# 3_STM32F334R8T6Board_FilterAndOutputs.net
KiCad netlist of a schematic drawn in Altium Designer
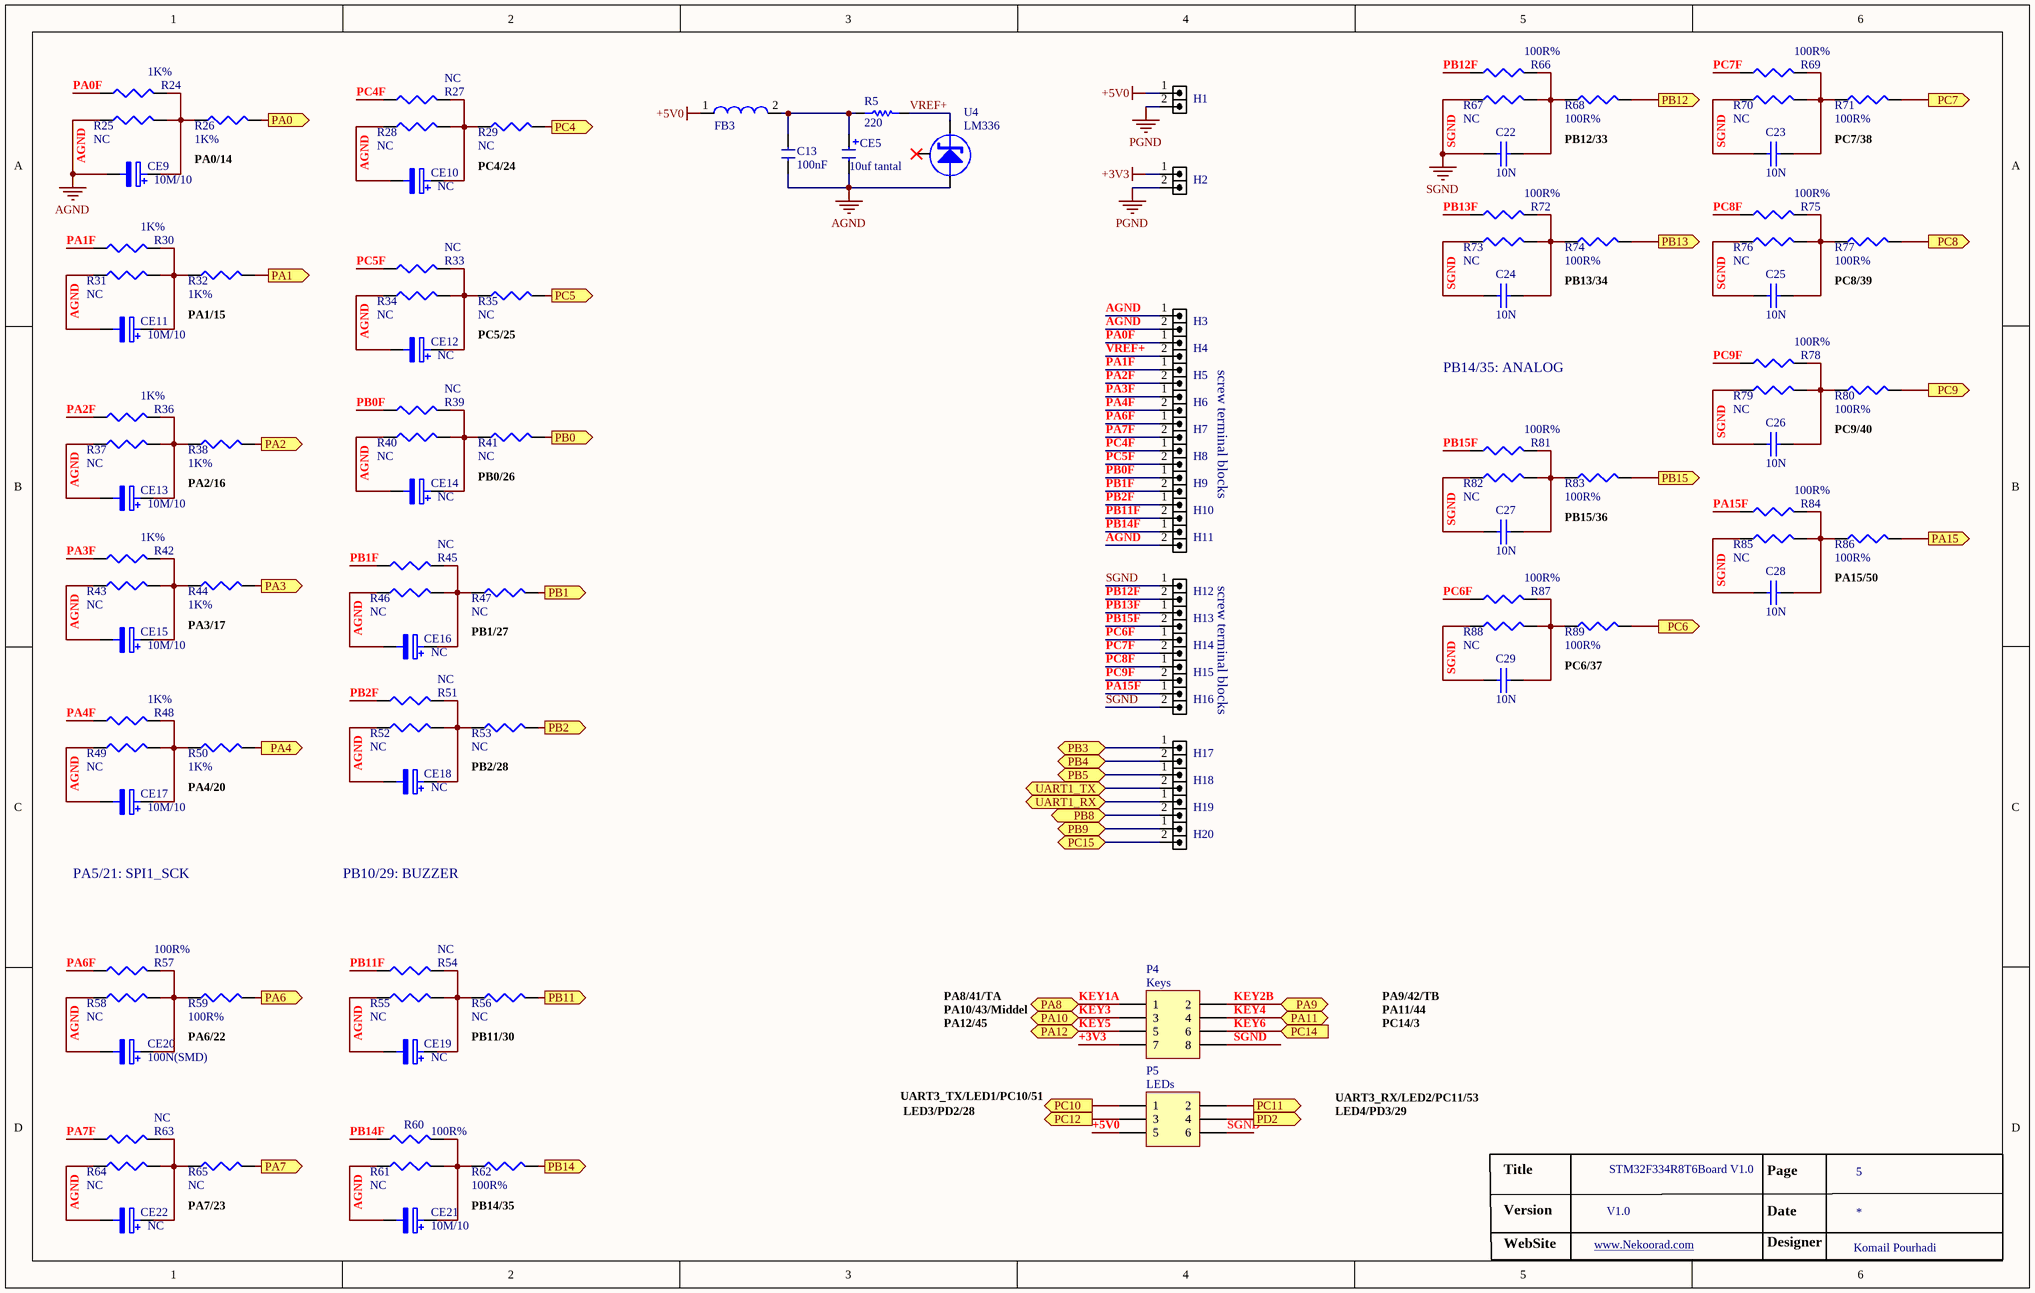
[diagram p0: [3]STM32F334R8T6Board_FilterAndOutputs.SchDoc]

(export (version "E")
  (design (tool "Eeschema 10.0.6"))
  (components
    (comp (ref "C13")
      (value "Comment")
      (footprint "SMD_CAP_1206")
      (fields (field (name "ALTIUM_UNNAMED_1") "100nF"))
      (libsource (lib "DotexGroup_LIB") (part "Capacitor SMD"))
    )
    (comp (ref "C22") (value "10N") (footprint "SMD_CAP_1206") (libsource (lib "*") (part "C")))
    (comp (ref "C23") (value "10N") (footprint "SMD_CAP_1206") (libsource (lib "*") (part "C")))
    (comp (ref "C24") (value "10N") (footprint "SMD_CAP_1206") (libsource (lib "*") (part "C")))
    (comp (ref "C25") (value "10N") (footprint "SMD_CAP_1206") (libsource (lib "*") (part "C")))
    (comp (ref "C26") (value "10N") (footprint "SMD_CAP_1206") (libsource (lib "*") (part "C")))
    (comp (ref "C27") (value "10N") (footprint "SMD_CAP_1206") (libsource (lib "*") (part "C")))
    (comp (ref "C28") (value "10N") (footprint "SMD_CAP_1206") (libsource (lib "*") (part "C")))
    (comp (ref "C29") (value "10N") (footprint "SMD_CAP_1206") (libsource (lib "*") (part "C")))
    (comp (ref "CE5")
      (value "10uf tantal")
      (footprint "cap-e-2")
      (libsource (lib "DotexGroup_LIB") (part "Capacitor Tantalium"))
    )
    (comp (ref "CE9") (value "10M/10") (footprint "CAP E+1206") (libsource (lib "*") (part "E")))
    (comp (ref "CE10") (value "NC") (footprint "CAP E+1206") (libsource (lib "*") (part "E")))
    (comp (ref "CE11") (value "10M/10") (footprint "CAP E+1206") (libsource (lib "*") (part "E")))
    (comp (ref "CE12") (value "NC") (footprint "CAP E+1206") (libsource (lib "*") (part "E")))
    (comp (ref "CE13") (value "10M/10") (footprint "CAP E+1206") (libsource (lib "*") (part "E")))
    (comp (ref "CE14") (value "NC") (footprint "CAP E+1206") (libsource (lib "*") (part "E")))
    (comp (ref "CE15") (value "10M/10") (footprint "CAP E+1206") (libsource (lib "*") (part "E")))
    (comp (ref "CE16") (value "NC") (footprint "CAP E+1206") (libsource (lib "*") (part "E")))
    (comp (ref "CE17") (value "10M/10") (footprint "CAP E+1206") (libsource (lib "*") (part "E")))
    (comp (ref "CE18") (value "NC") (footprint "CAP E+1206") (libsource (lib "*") (part "E")))
    (comp (ref "CE19") (value "NC") (footprint "CAP E+1206") (libsource (lib "*") (part "E")))
    (comp (ref "CE20") (value "100N(SMD)") (footprint "CAP E+1206") (libsource (lib "*") (part "E")))
    (comp (ref "CE21") (value "10M/10") (footprint "CAP E+1206") (libsource (lib "*") (part "E")))
    (comp (ref "CE22") (value "NC") (footprint "CAP E+1206") (libsource (lib "*") (part "E")))
    (comp (ref "FB3")
      (value "Comment")
      (footprint "r4p")
      (libsource (lib "DotexGroup_LIB") (part "Ferrit Bead"))
    )
    (comp (ref "H1")
      (value "HDRM2")
      (footprint "header screw 2*1")
      (description "CONN, HEADER, Male, pitch: 2.54mm, 2POS")
      (libsource (lib "conn_header") (part "HDR_M_1X2"))
    )
    (comp (ref "H2")
      (value "HDRM2")
      (footprint "header screw 2*1")
      (description "CONN, HEADER, Male, pitch: 2.54mm, 2POS")
      (libsource (lib "conn_header") (part "HDR_M_1X2"))
    )
    (comp (ref "H3")
      (value "HDRM2")
      (footprint "header screw 2*1")
      (description "CONN, HEADER, Male, pitch: 2.54mm, 2POS")
      (libsource (lib "conn_header") (part "HDR_M_1X2"))
    )
    (comp (ref "H4")
      (value "HDRM2")
      (footprint "header screw 2*1")
      (description "CONN, HEADER, Male, pitch: 2.54mm, 2POS")
      (libsource (lib "conn_header") (part "HDR_M_1X2"))
    )
    (comp (ref "H5")
      (value "HDRM2")
      (footprint "header screw 2*1")
      (description "CONN, HEADER, Male, pitch: 2.54mm, 2POS")
      (libsource (lib "conn_header") (part "HDR_M_1X2"))
    )
    (comp (ref "H6")
      (value "HDRM2")
      (footprint "header screw 2*1")
      (description "CONN, HEADER, Male, pitch: 2.54mm, 2POS")
      (libsource (lib "conn_header") (part "HDR_M_1X2"))
    )
    (comp (ref "H7")
      (value "HDRM2")
      (footprint "header screw 2*1")
      (description "CONN, HEADER, Male, pitch: 2.54mm, 2POS")
      (libsource (lib "conn_header") (part "HDR_M_1X2"))
    )
    (comp (ref "H8")
      (value "HDRM2")
      (footprint "header screw 2*1")
      (description "CONN, HEADER, Male, pitch: 2.54mm, 2POS")
      (libsource (lib "conn_header") (part "HDR_M_1X2"))
    )
    (comp (ref "H9")
      (value "HDRM2")
      (footprint "header screw 2*1")
      (description "CONN, HEADER, Male, pitch: 2.54mm, 2POS")
      (libsource (lib "conn_header") (part "HDR_M_1X2"))
    )
    (comp (ref "H10")
      (value "HDRM2")
      (footprint "header screw 2*1")
      (description "CONN, HEADER, Male, pitch: 2.54mm, 2POS")
      (libsource (lib "conn_header") (part "HDR_M_1X2"))
    )
    (comp (ref "H11")
      (value "HDRM2")
      (footprint "header screw 2*1")
      (description "CONN, HEADER, Male, pitch: 2.54mm, 2POS")
      (libsource (lib "conn_header") (part "HDR_M_1X2"))
    )
    (comp (ref "H12")
      (value "HDRM2")
      (footprint "header screw 2*1")
      (description "CONN, HEADER, Male, pitch: 2.54mm, 2POS")
      (libsource (lib "conn_header") (part "HDR_M_1X2"))
    )
    (comp (ref "H13")
      (value "HDRM2")
      (footprint "header screw 2*1")
      (description "CONN, HEADER, Male, pitch: 2.54mm, 2POS")
      (libsource (lib "conn_header") (part "HDR_M_1X2"))
    )
    (comp (ref "H14")
      (value "HDRM2")
      (footprint "header screw 2*1")
      (description "CONN, HEADER, Male, pitch: 2.54mm, 2POS")
      (libsource (lib "conn_header") (part "HDR_M_1X2"))
    )
    (comp (ref "H15")
      (value "HDRM2")
      (footprint "header screw 2*1")
      (description "CONN, HEADER, Male, pitch: 2.54mm, 2POS")
      (libsource (lib "conn_header") (part "HDR_M_1X2"))
    )
    (comp (ref "H16")
      (value "HDRM2")
      (footprint "header screw 2*1")
      (description "CONN, HEADER, Male, pitch: 2.54mm, 2POS")
      (libsource (lib "conn_header") (part "HDR_M_1X2"))
    )
    (comp (ref "H17")
      (value "HDRM2")
      (footprint "header screw 2*1")
      (description "CONN, HEADER, Male, pitch: 2.54mm, 2POS")
      (libsource (lib "conn_header") (part "HDR_M_1X2"))
    )
    (comp (ref "H18")
      (value "HDRM2")
      (footprint "header screw 2*1")
      (description "CONN, HEADER, Male, pitch: 2.54mm, 2POS")
      (libsource (lib "conn_header") (part "HDR_M_1X2"))
    )
    (comp (ref "H19")
      (value "HDRM2")
      (footprint "header screw 2*1")
      (description "CONN, HEADER, Male, pitch: 2.54mm, 2POS")
      (libsource (lib "conn_header") (part "HDR_M_1X2"))
    )
    (comp (ref "H20")
      (value "HDRM2")
      (footprint "header screw 2*1")
      (description "CONN, HEADER, Male, pitch: 2.54mm, 2POS")
      (libsource (lib "conn_header") (part "HDR_M_1X2"))
    )
    (comp (ref "P4")
      (value "Keys")
      (footprint "IDC8-BOX")
      (description "Header, 4-Pin, Dual row")
      (fields (field (name "PUBLISHER") "Altium Limited"))
      (libsource (lib "Miscellaneous Connectors") (part "Header 4X2"))
    )
    (comp (ref "P5")
      (value "LEDs")
      (footprint "IDC6-BOX")
      (description "Header, 3-Pin, Dual row")
      (fields (field (name "PUBLISHER") "Altium Limited"))
      (libsource (lib "Miscellaneous Connectors") (part "Header 3X2"))
    )
    (comp (ref "R5")
      (value "220")
      (footprint "RES_1206")
      (description "Resistor")
      (fields (field (name "TOLERANCE") "5%") (field (name "POWER") "1/8 W"))
      (libsource (lib "My Library") (part "Resistor"))
    )
    (comp (ref "R24") (value "1K%") (footprint "RES_1206") (libsource (lib "*") (part "R")))
    (comp (ref "R25") (value "NC") (footprint "RES_1206") (libsource (lib "*") (part "R")))
    (comp (ref "R26") (value "1K%") (footprint "RES_1206") (libsource (lib "*") (part "R")))
    (comp (ref "R27") (value "NC") (footprint "RES_1206") (libsource (lib "*") (part "R")))
    (comp (ref "R28") (value "NC") (footprint "RES_1206") (libsource (lib "*") (part "R")))
    (comp (ref "R29") (value "NC") (footprint "RES_1206") (libsource (lib "*") (part "R")))
    (comp (ref "R30") (value "1K%") (footprint "RES_1206") (libsource (lib "*") (part "R")))
    (comp (ref "R31") (value "NC") (footprint "RES_1206") (libsource (lib "*") (part "R")))
    (comp (ref "R32") (value "1K%") (footprint "RES_1206") (libsource (lib "*") (part "R")))
    (comp (ref "R33") (value "NC") (footprint "RES_1206") (libsource (lib "*") (part "R")))
    (comp (ref "R34") (value "NC") (footprint "RES_1206") (libsource (lib "*") (part "R")))
    (comp (ref "R35") (value "NC") (footprint "RES_1206") (libsource (lib "*") (part "R")))
    (comp (ref "R36") (value "1K%") (footprint "RES_1206") (libsource (lib "*") (part "R")))
    (comp (ref "R37") (value "NC") (footprint "RES_1206") (libsource (lib "*") (part "R")))
    (comp (ref "R38") (value "1K%") (footprint "RES_1206") (libsource (lib "*") (part "R")))
    (comp (ref "R39") (value "NC") (footprint "RES_1206") (libsource (lib "*") (part "R")))
    (comp (ref "R40") (value "NC") (footprint "RES_1206") (libsource (lib "*") (part "R")))
    (comp (ref "R41") (value "NC") (footprint "RES_1206") (libsource (lib "*") (part "R")))
    (comp (ref "R42") (value "1K%") (footprint "RES_1206") (libsource (lib "*") (part "R")))
    (comp (ref "R43") (value "NC") (footprint "RES_1206") (libsource (lib "*") (part "R")))
    (comp (ref "R44") (value "1K%") (footprint "RES_1206") (libsource (lib "*") (part "R")))
    (comp (ref "R45") (value "NC") (footprint "RES_1206") (libsource (lib "*") (part "R")))
    (comp (ref "R46") (value "NC") (footprint "RES_1206") (libsource (lib "*") (part "R")))
    (comp (ref "R47") (value "NC") (footprint "RES_1206") (libsource (lib "*") (part "R")))
    (comp (ref "R48") (value "1K%") (footprint "RES_1206") (libsource (lib "*") (part "R")))
    (comp (ref "R49") (value "NC") (footprint "RES_1206") (libsource (lib "*") (part "R")))
    (comp (ref "R50") (value "1K%") (footprint "RES_1206") (libsource (lib "*") (part "R")))
    (comp (ref "R51") (value "NC") (footprint "RES_1206") (libsource (lib "*") (part "R")))
    (comp (ref "R52") (value "NC") (footprint "RES_1206") (libsource (lib "*") (part "R")))
    (comp (ref "R53") (value "NC") (footprint "RES_1206") (libsource (lib "*") (part "R")))
    (comp (ref "R54") (value "NC") (footprint "RES_1206") (libsource (lib "*") (part "R")))
    (comp (ref "R55") (value "NC") (footprint "RES_1206") (libsource (lib "*") (part "R")))
    (comp (ref "R56") (value "NC") (footprint "RES_1206") (libsource (lib "*") (part "R")))
    (comp (ref "R57") (value "100R%") (footprint "RES_1206") (libsource (lib "*") (part "R")))
    (comp (ref "R58") (value "NC") (footprint "RES_1206") (libsource (lib "*") (part "R")))
    (comp (ref "R59") (value "100R%") (footprint "RES_1206") (libsource (lib "*") (part "R")))
    (comp (ref "R60") (value "100R%") (footprint "RES_1206") (libsource (lib "*") (part "R")))
    (comp (ref "R61") (value "NC") (footprint "RES_1206") (libsource (lib "*") (part "R")))
    (comp (ref "R62") (value "100R%") (footprint "RES_1206") (libsource (lib "*") (part "R")))
    (comp (ref "R63") (value "NC") (footprint "RES_1206") (libsource (lib "*") (part "R")))
    (comp (ref "R64") (value "NC") (footprint "RES_1206") (libsource (lib "*") (part "R")))
    (comp (ref "R65") (value "NC") (footprint "RES_1206") (libsource (lib "*") (part "R")))
    (comp (ref "R66") (value "100R%") (footprint "RES_1206") (libsource (lib "*") (part "R")))
    (comp (ref "R67") (value "NC") (footprint "RES_1206") (libsource (lib "*") (part "R")))
    (comp (ref "R68") (value "100R%") (footprint "RES_1206") (libsource (lib "*") (part "R")))
    (comp (ref "R69") (value "100R%") (footprint "RES_1206") (libsource (lib "*") (part "R")))
    (comp (ref "R70") (value "NC") (footprint "RES_1206") (libsource (lib "*") (part "R")))
    (comp (ref "R71") (value "100R%") (footprint "RES_1206") (libsource (lib "*") (part "R")))
    (comp (ref "R72") (value "100R%") (footprint "RES_1206") (libsource (lib "*") (part "R")))
    (comp (ref "R73") (value "NC") (footprint "RES_1206") (libsource (lib "*") (part "R")))
    (comp (ref "R74") (value "100R%") (footprint "RES_1206") (libsource (lib "*") (part "R")))
    (comp (ref "R75") (value "100R%") (footprint "RES_1206") (libsource (lib "*") (part "R")))
    (comp (ref "R76") (value "NC") (footprint "RES_1206") (libsource (lib "*") (part "R")))
    (comp (ref "R77") (value "100R%") (footprint "RES_1206") (libsource (lib "*") (part "R")))
    (comp (ref "R78") (value "100R%") (footprint "RES_1206") (libsource (lib "*") (part "R")))
    (comp (ref "R79") (value "NC") (footprint "RES_1206") (libsource (lib "*") (part "R")))
    (comp (ref "R80") (value "100R%") (footprint "RES_1206") (libsource (lib "*") (part "R")))
    (comp (ref "R81") (value "100R%") (footprint "RES_1206") (libsource (lib "*") (part "R")))
    (comp (ref "R82") (value "NC") (footprint "RES_1206") (libsource (lib "*") (part "R")))
    (comp (ref "R83") (value "100R%") (footprint "RES_1206") (libsource (lib "*") (part "R")))
    (comp (ref "R84") (value "100R%") (footprint "RES_1206") (libsource (lib "*") (part "R")))
    (comp (ref "R85") (value "NC") (footprint "RES_1206") (libsource (lib "*") (part "R")))
    (comp (ref "R86") (value "100R%") (footprint "RES_1206") (libsource (lib "*") (part "R")))
    (comp (ref "R87") (value "100R%") (footprint "RES_1206") (libsource (lib "*") (part "R")))
    (comp (ref "R88") (value "NC") (footprint "RES_1206") (libsource (lib "*") (part "R")))
    (comp (ref "R89") (value "100R%") (footprint "RES_1206") (libsource (lib "*") (part "R")))
    (comp (ref "U4") (value "LM336") (footprint "LM336") (libsource (lib "MyAltiumLib") (part "LM336")))
  )
  (nets
    (net (code "1") (name "+3V3") (class "Default")
      (node (ref "H2") (pin "1") (pinfunction "1_1") (pintype "passive"))
      (node (ref "P4") (pin "7") (pinfunction "7_7") (pintype "passive"))
    )
    (net (code "2") (name "+5V0") (class "Default")
      (node (ref "FB3") (pin "1") (pinfunction "1_1") (pintype "passive"))
      (node (ref "H1") (pin "1") (pinfunction "1_1") (pintype "passive"))
      (node (ref "P5") (pin "5") (pinfunction "5_5") (pintype "passive"))
    )
    (net (code "3") (name "/KEY1A") (class "Default")
      (node (ref "P4") (pin "1") (pinfunction "1_1") (pintype "passive"))
    )
    (net (code "4") (name "/KEY2B") (class "Default")
      (node (ref "P4") (pin "2") (pinfunction "2_2") (pintype "passive"))
    )
    (net (code "5") (name "/KEY3") (class "Default")
      (node (ref "P4") (pin "3") (pinfunction "3_3") (pintype "passive"))
    )
    (net (code "6") (name "/KEY4") (class "Default")
      (node (ref "P4") (pin "4") (pinfunction "4_4") (pintype "passive"))
    )
    (net (code "7") (name "/KEY5") (class "Default")
      (node (ref "P4") (pin "5") (pinfunction "5_5") (pintype "passive"))
    )
    (net (code "8") (name "/KEY6") (class "Default")
      (node (ref "P4") (pin "6") (pinfunction "6_6") (pintype "passive"))
    )
    (net (code "9") (name "/PA0") (class "Default") (node (ref "R26") (pin "2") (pintype "passive")))
    (net (code "10") (name "/PA0F") (class "Default")
      (node (ref "H4") (pin "1") (pinfunction "1_1") (pintype "passive"))
      (node (ref "R24") (pin "1") (pintype "passive"))
    )
    (net (code "11") (name "/PA1") (class "Default") (node (ref "R32") (pin "2") (pintype "passive")))
    (net (code "12") (name "/PA1F") (class "Default")
      (node (ref "H5") (pin "1") (pinfunction "1_1") (pintype "passive"))
      (node (ref "R30") (pin "1") (pintype "passive"))
    )
    (net (code "13") (name "/PA2") (class "Default") (node (ref "R38") (pin "2") (pintype "passive")))
    (net (code "14") (name "/PA2F") (class "Default")
      (node (ref "H5") (pin "2") (pinfunction "2_2") (pintype "passive"))
      (node (ref "R36") (pin "1") (pintype "passive"))
    )
    (net (code "15") (name "/PA3") (class "Default") (node (ref "R44") (pin "2") (pintype "passive")))
    (net (code "16") (name "/PA3F") (class "Default")
      (node (ref "H6") (pin "1") (pinfunction "1_1") (pintype "passive"))
      (node (ref "R42") (pin "1") (pintype "passive"))
    )
    (net (code "17") (name "/PA4") (class "Default") (node (ref "R50") (pin "2") (pintype "passive")))
    (net (code "18") (name "/PA4F") (class "Default")
      (node (ref "H6") (pin "2") (pinfunction "2_2") (pintype "passive"))
      (node (ref "R48") (pin "1") (pintype "passive"))
    )
    (net (code "19") (name "/PA6") (class "Default") (node (ref "R59") (pin "2") (pintype "passive")))
    (net (code "20") (name "/PA6F") (class "Default")
      (node (ref "H7") (pin "1") (pinfunction "1_1") (pintype "passive"))
      (node (ref "R57") (pin "1") (pintype "passive"))
    )
    (net (code "21") (name "/PA7") (class "Default") (node (ref "R65") (pin "2") (pintype "passive")))
    (net (code "22") (name "/PA7F") (class "Default")
      (node (ref "H7") (pin "2") (pinfunction "2_2") (pintype "passive"))
      (node (ref "R63") (pin "1") (pintype "passive"))
    )
    (net (code "23") (name "/PA15") (class "Default") (node (ref "R86") (pin "2") (pintype "passive")))
    (net (code "24") (name "/PA15F") (class "Default")
      (node (ref "H16") (pin "1") (pinfunction "1_1") (pintype "passive"))
      (node (ref "R84") (pin "1") (pintype "passive"))
    )
    (net (code "25") (name "/PB0") (class "Default") (node (ref "R41") (pin "2") (pintype "passive")))
    (net (code "26") (name "/PB0F") (class "Default")
      (node (ref "H9") (pin "1") (pinfunction "1_1") (pintype "passive"))
      (node (ref "R39") (pin "1") (pintype "passive"))
    )
    (net (code "27") (name "/PB1") (class "Default") (node (ref "R47") (pin "2") (pintype "passive")))
    (net (code "28") (name "/PB1F") (class "Default")
      (node (ref "H9") (pin "2") (pinfunction "2_2") (pintype "passive"))
      (node (ref "R45") (pin "1") (pintype "passive"))
    )
    (net (code "29") (name "/PB2") (class "Default") (node (ref "R53") (pin "2") (pintype "passive")))
    (net (code "30") (name "/PB2F") (class "Default")
      (node (ref "H10") (pin "1") (pinfunction "1_1") (pintype "passive"))
      (node (ref "R51") (pin "1") (pintype "passive"))
    )
    (net (code "31") (name "/PB3") (class "Default")
      (node (ref "H17") (pin "1") (pinfunction "1_1") (pintype "passive"))
    )
    (net (code "32") (name "/PB4") (class "Default")
      (node (ref "H17") (pin "2") (pinfunction "2_2") (pintype "passive"))
    )
    (net (code "33") (name "/PB5") (class "Default")
      (node (ref "H18") (pin "1") (pinfunction "1_1") (pintype "passive"))
    )
    (net (code "34") (name "/PB8") (class "Default")
      (node (ref "H19") (pin "2") (pinfunction "2_2") (pintype "passive"))
    )
    (net (code "35") (name "/PB9") (class "Default")
      (node (ref "H20") (pin "1") (pinfunction "1_1") (pintype "passive"))
    )
    (net (code "36") (name "/PB11") (class "Default") (node (ref "R56") (pin "2") (pintype "passive")))
    (net (code "37") (name "/PB11F") (class "Default")
      (node (ref "H10") (pin "2") (pinfunction "2_2") (pintype "passive"))
      (node (ref "R54") (pin "1") (pintype "passive"))
    )
    (net (code "38") (name "/PB12") (class "Default") (node (ref "R68") (pin "2") (pintype "passive")))
    (net (code "39") (name "/PB12F") (class "Default")
      (node (ref "H12") (pin "2") (pinfunction "2_2") (pintype "passive"))
      (node (ref "R66") (pin "1") (pintype "passive"))
    )
    (net (code "40") (name "/PB13") (class "Default") (node (ref "R74") (pin "2") (pintype "passive")))
    (net (code "41") (name "/PB13F") (class "Default")
      (node (ref "H13") (pin "1") (pinfunction "1_1") (pintype "passive"))
      (node (ref "R72") (pin "1") (pintype "passive"))
    )
    (net (code "42") (name "/PB14") (class "Default") (node (ref "R62") (pin "2") (pintype "passive")))
    (net (code "43") (name "/PB14F") (class "Default")
      (node (ref "H11") (pin "1") (pinfunction "1_1") (pintype "passive"))
      (node (ref "R60") (pin "1") (pintype "passive"))
    )
    (net (code "44") (name "/PB15") (class "Default") (node (ref "R83") (pin "2") (pintype "passive")))
    (net (code "45") (name "/PB15F") (class "Default")
      (node (ref "H13") (pin "2") (pinfunction "2_2") (pintype "passive"))
      (node (ref "R81") (pin "1") (pintype "passive"))
    )
    (net (code "46") (name "/PC4") (class "Default") (node (ref "R29") (pin "2") (pintype "passive")))
    (net (code "47") (name "/PC4F") (class "Default")
      (node (ref "H8") (pin "1") (pinfunction "1_1") (pintype "passive"))
      (node (ref "R27") (pin "1") (pintype "passive"))
    )
    (net (code "48") (name "/PC5") (class "Default") (node (ref "R35") (pin "2") (pintype "passive")))
    (net (code "49") (name "/PC5F") (class "Default")
      (node (ref "H8") (pin "2") (pinfunction "2_2") (pintype "passive"))
      (node (ref "R33") (pin "1") (pintype "passive"))
    )
    (net (code "50") (name "/PC6") (class "Default") (node (ref "R89") (pin "2") (pintype "passive")))
    (net (code "51") (name "/PC6F") (class "Default")
      (node (ref "H14") (pin "1") (pinfunction "1_1") (pintype "passive"))
      (node (ref "R87") (pin "1") (pintype "passive"))
    )
    (net (code "52") (name "/PC7") (class "Default") (node (ref "R71") (pin "2") (pintype "passive")))
    (net (code "53") (name "/PC7F") (class "Default")
      (node (ref "H14") (pin "2") (pinfunction "2_2") (pintype "passive"))
      (node (ref "R69") (pin "1") (pintype "passive"))
    )
    (net (code "54") (name "/PC8") (class "Default") (node (ref "R77") (pin "2") (pintype "passive")))
    (net (code "55") (name "/PC8F") (class "Default")
      (node (ref "H15") (pin "1") (pinfunction "1_1") (pintype "passive"))
      (node (ref "R75") (pin "1") (pintype "passive"))
    )
    (net (code "56") (name "/PC9") (class "Default") (node (ref "R80") (pin "2") (pintype "passive")))
    (net (code "57") (name "/PC9F") (class "Default")
      (node (ref "H15") (pin "2") (pinfunction "2_2") (pintype "passive"))
      (node (ref "R78") (pin "1") (pintype "passive"))
    )
    (net (code "58") (name "/PC10") (class "Default")
      (node (ref "P5") (pin "1") (pinfunction "1_1") (pintype "passive"))
    )
    (net (code "59") (name "/PC11") (class "Default")
      (node (ref "P5") (pin "2") (pinfunction "2_2") (pintype "passive"))
    )
    (net (code "60") (name "/PC12") (class "Default")
      (node (ref "P5") (pin "3") (pinfunction "3_3") (pintype "passive"))
    )
    (net (code "61") (name "/PC15") (class "Default")
      (node (ref "H20") (pin "2") (pinfunction "2_2") (pintype "passive"))
    )
    (net (code "62") (name "/PD2") (class "Default")
      (node (ref "P5") (pin "4") (pinfunction "4_4") (pintype "passive"))
    )
    (net (code "63") (name "/UART1_RX") (class "Default")
      (node (ref "H19") (pin "1") (pinfunction "1_1") (pintype "passive"))
    )
    (net (code "64") (name "/UART1_TX") (class "Default")
      (node (ref "H18") (pin "2") (pinfunction "2_2") (pintype "passive"))
    )
    (net (code "65") (name "/VREF+") (class "Default")
      (node (ref "H4") (pin "2") (pinfunction "2_2") (pintype "passive"))
      (node (ref "R5") (pin "2") (pinfunction "2_2") (pintype "passive"))
      (node (ref "U4") (pin "2") (pintype "passive"))
    )
    (net (code "66") (name "AGND") (class "Default")
      (node (ref "C13") (pin "1") (pintype "passive"))
      (node (ref "CE10") (pin "2") (pintype "passive"))
      (node (ref "CE11") (pin "2") (pintype "passive"))
      (node (ref "CE12") (pin "2") (pintype "passive"))
      (node (ref "CE13") (pin "2") (pintype "passive"))
      (node (ref "CE14") (pin "2") (pintype "passive"))
      (node (ref "CE15") (pin "2") (pintype "passive"))
      (node (ref "CE16") (pin "2") (pintype "passive"))
      (node (ref "CE17") (pin "2") (pintype "passive"))
      (node (ref "CE18") (pin "2") (pintype "passive"))
      (node (ref "CE19") (pin "2") (pintype "passive"))
      (node (ref "CE20") (pin "2") (pintype "passive"))
      (node (ref "CE21") (pin "2") (pintype "passive"))
      (node (ref "CE22") (pin "2") (pintype "passive"))
      (node (ref "CE5") (pin "2") (pintype "passive"))
      (node (ref "CE9") (pin "2") (pintype "passive"))
      (node (ref "H11") (pin "2") (pinfunction "2_2") (pintype "passive"))
      (node (ref "H3") (pin "1") (pinfunction "1_1") (pintype "passive"))
      (node (ref "H3") (pin "2") (pinfunction "2_2") (pintype "passive"))
      (node (ref "R25") (pin "1") (pintype "passive"))
      (node (ref "R28") (pin "1") (pintype "passive"))
      (node (ref "R31") (pin "1") (pintype "passive"))
      (node (ref "R34") (pin "1") (pintype "passive"))
      (node (ref "R37") (pin "1") (pintype "passive"))
      (node (ref "R40") (pin "1") (pintype "passive"))
      (node (ref "R43") (pin "1") (pintype "passive"))
      (node (ref "R46") (pin "1") (pintype "passive"))
      (node (ref "R49") (pin "1") (pintype "passive"))
      (node (ref "R52") (pin "1") (pintype "passive"))
      (node (ref "R55") (pin "1") (pintype "passive"))
      (node (ref "R58") (pin "1") (pintype "passive"))
      (node (ref "R61") (pin "1") (pintype "passive"))
      (node (ref "R64") (pin "1") (pintype "passive"))
      (node (ref "U4") (pin "1") (pintype "passive"))
    )
    (net (code "67") (name "Net-(C13-Pad2)") (class "Default")
      (node (ref "C13") (pin "2") (pintype "passive"))
      (node (ref "CE5") (pin "1") (pintype "passive"))
      (node (ref "FB3") (pin "2") (pinfunction "2_2") (pintype "passive"))
      (node (ref "R5") (pin "1") (pinfunction "1_1") (pintype "passive"))
    )
    (net (code "68") (name "Net-(C22-Pad1)") (class "Default")
      (node (ref "C22") (pin "1") (pintype "passive"))
      (node (ref "R66") (pin "2") (pintype "passive"))
      (node (ref "R67") (pin "2") (pintype "passive"))
      (node (ref "R68") (pin "1") (pintype "passive"))
    )
    (net (code "69") (name "Net-(C23-Pad1)") (class "Default")
      (node (ref "C23") (pin "1") (pintype "passive"))
      (node (ref "R69") (pin "2") (pintype "passive"))
      (node (ref "R70") (pin "2") (pintype "passive"))
      (node (ref "R71") (pin "1") (pintype "passive"))
    )
    (net (code "70") (name "Net-(C24-Pad1)") (class "Default")
      (node (ref "C24") (pin "1") (pintype "passive"))
      (node (ref "R72") (pin "2") (pintype "passive"))
      (node (ref "R73") (pin "2") (pintype "passive"))
      (node (ref "R74") (pin "1") (pintype "passive"))
    )
    (net (code "71") (name "Net-(C25-Pad1)") (class "Default")
      (node (ref "C25") (pin "1") (pintype "passive"))
      (node (ref "R75") (pin "2") (pintype "passive"))
      (node (ref "R76") (pin "2") (pintype "passive"))
      (node (ref "R77") (pin "1") (pintype "passive"))
    )
    (net (code "72") (name "Net-(C26-Pad1)") (class "Default")
      (node (ref "C26") (pin "1") (pintype "passive"))
      (node (ref "R78") (pin "2") (pintype "passive"))
      (node (ref "R79") (pin "2") (pintype "passive"))
      (node (ref "R80") (pin "1") (pintype "passive"))
    )
    (net (code "73") (name "Net-(C27-Pad1)") (class "Default")
      (node (ref "C27") (pin "1") (pintype "passive"))
      (node (ref "R81") (pin "2") (pintype "passive"))
      (node (ref "R82") (pin "2") (pintype "passive"))
      (node (ref "R83") (pin "1") (pintype "passive"))
    )
    (net (code "74") (name "Net-(C28-Pad1)") (class "Default")
      (node (ref "C28") (pin "1") (pintype "passive"))
      (node (ref "R84") (pin "2") (pintype "passive"))
      (node (ref "R85") (pin "2") (pintype "passive"))
      (node (ref "R86") (pin "1") (pintype "passive"))
    )
    (net (code "75") (name "Net-(C29-Pad1)") (class "Default")
      (node (ref "C29") (pin "1") (pintype "passive"))
      (node (ref "R87") (pin "2") (pintype "passive"))
      (node (ref "R88") (pin "2") (pintype "passive"))
      (node (ref "R89") (pin "1") (pintype "passive"))
    )
    (net (code "76") (name "Net-(CE9-Pad1)") (class "Default")
      (node (ref "CE9") (pin "1") (pintype "passive"))
      (node (ref "R24") (pin "2") (pintype "passive"))
      (node (ref "R25") (pin "2") (pintype "passive"))
      (node (ref "R26") (pin "1") (pintype "passive"))
    )
    (net (code "77") (name "Net-(CE10-Pad1)") (class "Default")
      (node (ref "CE10") (pin "1") (pintype "passive"))
      (node (ref "R27") (pin "2") (pintype "passive"))
      (node (ref "R28") (pin "2") (pintype "passive"))
      (node (ref "R29") (pin "1") (pintype "passive"))
    )
    (net (code "78") (name "Net-(CE11-Pad1)") (class "Default")
      (node (ref "CE11") (pin "1") (pintype "passive"))
      (node (ref "R30") (pin "2") (pintype "passive"))
      (node (ref "R31") (pin "2") (pintype "passive"))
      (node (ref "R32") (pin "1") (pintype "passive"))
    )
    (net (code "79") (name "Net-(CE12-Pad1)") (class "Default")
      (node (ref "CE12") (pin "1") (pintype "passive"))
      (node (ref "R33") (pin "2") (pintype "passive"))
      (node (ref "R34") (pin "2") (pintype "passive"))
      (node (ref "R35") (pin "1") (pintype "passive"))
    )
    (net (code "80") (name "Net-(CE13-Pad1)") (class "Default")
      (node (ref "CE13") (pin "1") (pintype "passive"))
      (node (ref "R36") (pin "2") (pintype "passive"))
      (node (ref "R37") (pin "2") (pintype "passive"))
      (node (ref "R38") (pin "1") (pintype "passive"))
    )
    (net (code "81") (name "Net-(CE14-Pad1)") (class "Default")
      (node (ref "CE14") (pin "1") (pintype "passive"))
      (node (ref "R39") (pin "2") (pintype "passive"))
      (node (ref "R40") (pin "2") (pintype "passive"))
      (node (ref "R41") (pin "1") (pintype "passive"))
    )
    (net (code "82") (name "Net-(CE15-Pad1)") (class "Default")
      (node (ref "CE15") (pin "1") (pintype "passive"))
      (node (ref "R42") (pin "2") (pintype "passive"))
      (node (ref "R43") (pin "2") (pintype "passive"))
      (node (ref "R44") (pin "1") (pintype "passive"))
    )
    (net (code "83") (name "Net-(CE16-Pad1)") (class "Default")
      (node (ref "CE16") (pin "1") (pintype "passive"))
      (node (ref "R45") (pin "2") (pintype "passive"))
      (node (ref "R46") (pin "2") (pintype "passive"))
      (node (ref "R47") (pin "1") (pintype "passive"))
    )
    (net (code "84") (name "Net-(CE17-Pad1)") (class "Default")
      (node (ref "CE17") (pin "1") (pintype "passive"))
      (node (ref "R48") (pin "2") (pintype "passive"))
      (node (ref "R49") (pin "2") (pintype "passive"))
      (node (ref "R50") (pin "1") (pintype "passive"))
    )
    (net (code "85") (name "Net-(CE18-Pad1)") (class "Default")
      (node (ref "CE18") (pin "1") (pintype "passive"))
      (node (ref "R51") (pin "2") (pintype "passive"))
      (node (ref "R52") (pin "2") (pintype "passive"))
      (node (ref "R53") (pin "1") (pintype "passive"))
    )
    (net (code "86") (name "Net-(CE19-Pad1)") (class "Default")
      (node (ref "CE19") (pin "1") (pintype "passive"))
      (node (ref "R54") (pin "2") (pintype "passive"))
      (node (ref "R55") (pin "2") (pintype "passive"))
      (node (ref "R56") (pin "1") (pintype "passive"))
    )
    (net (code "87") (name "Net-(CE20-Pad1)") (class "Default")
      (node (ref "CE20") (pin "1") (pintype "passive"))
      (node (ref "R57") (pin "2") (pintype "passive"))
      (node (ref "R58") (pin "2") (pintype "passive"))
      (node (ref "R59") (pin "1") (pintype "passive"))
    )
    (net (code "88") (name "Net-(CE21-Pad1)") (class "Default")
      (node (ref "CE21") (pin "1") (pintype "passive"))
      (node (ref "R60") (pin "2") (pintype "passive"))
      (node (ref "R61") (pin "2") (pintype "passive"))
      (node (ref "R62") (pin "1") (pintype "passive"))
    )
    (net (code "89") (name "Net-(CE22-Pad1)") (class "Default")
      (node (ref "CE22") (pin "1") (pintype "passive"))
      (node (ref "R63") (pin "2") (pintype "passive"))
      (node (ref "R64") (pin "2") (pintype "passive"))
      (node (ref "R65") (pin "1") (pintype "passive"))
    )
    (net (code "90") (name "PGND") (class "Default")
      (node (ref "H1") (pin "2") (pinfunction "2_2") (pintype "passive"))
      (node (ref "H2") (pin "2") (pinfunction "2_2") (pintype "passive"))
    )
    (net (code "91") (name "SGND") (class "Default")
      (node (ref "C22") (pin "2") (pintype "passive"))
      (node (ref "C23") (pin "2") (pintype "passive"))
      (node (ref "C24") (pin "2") (pintype "passive"))
      (node (ref "C25") (pin "2") (pintype "passive"))
      (node (ref "C26") (pin "2") (pintype "passive"))
      (node (ref "C27") (pin "2") (pintype "passive"))
      (node (ref "C28") (pin "2") (pintype "passive"))
      (node (ref "C29") (pin "2") (pintype "passive"))
      (node (ref "H12") (pin "1") (pinfunction "1_1") (pintype "passive"))
      (node (ref "H16") (pin "2") (pinfunction "2_2") (pintype "passive"))
      (node (ref "P4") (pin "8") (pinfunction "8_8") (pintype "passive"))
      (node (ref "P5") (pin "6") (pinfunction "6_6") (pintype "passive"))
      (node (ref "R67") (pin "1") (pintype "passive"))
      (node (ref "R70") (pin "1") (pintype "passive"))
      (node (ref "R73") (pin "1") (pintype "passive"))
      (node (ref "R76") (pin "1") (pintype "passive"))
      (node (ref "R79") (pin "1") (pintype "passive"))
      (node (ref "R82") (pin "1") (pintype "passive"))
      (node (ref "R85") (pin "1") (pintype "passive"))
      (node (ref "R88") (pin "1") (pintype "passive"))
    )
    (net (code "92") (name "unconnected-(U4-Pad3)") (class "Default")
      (node (ref "U4") (pin "3") (pintype "passive+no_connect"))
    )
  )
)
